# ETH.net
KiCad netlist of a schematic drawn in Altium Designer
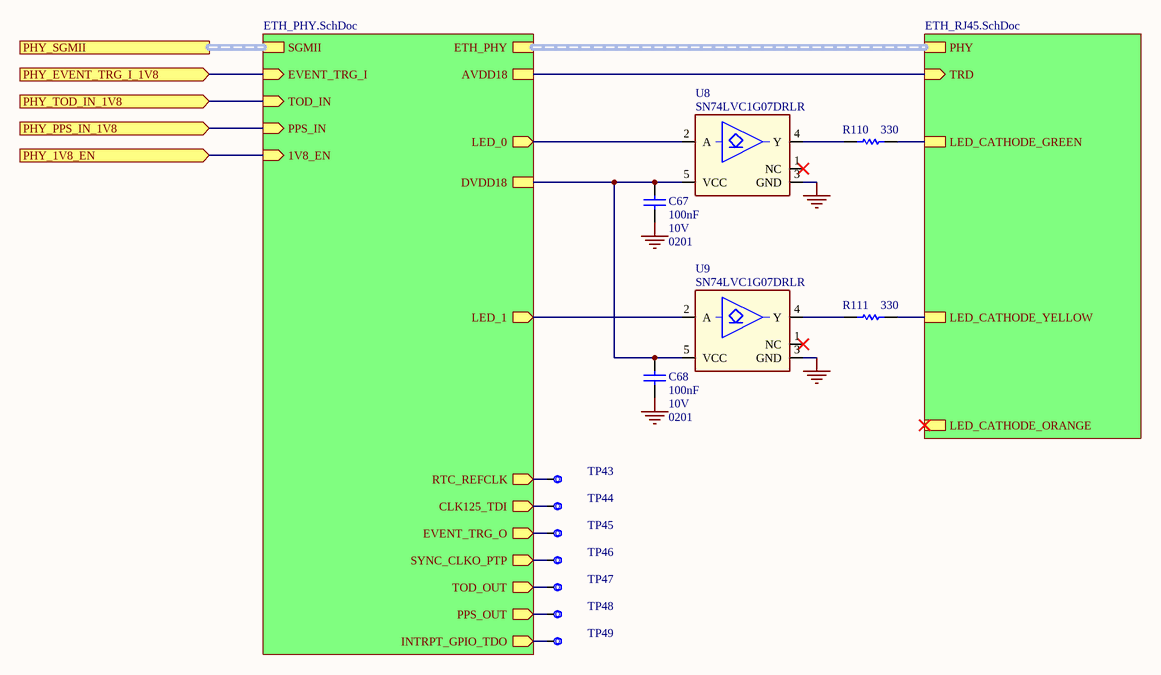
[diagram p0: ETH.SchDoc]

(export (version "E")
  (design (tool "Eeschema 10.0.6"))
  (components
    (comp (ref "C67")
      (value "100nF")
      (footprint "CAP-0201")
      (description "CAP CHIP 0201 100nF 10% 10V X5R")
      (fields
        (field (name "PART NUMBER") "CL03A104KP3NNNC")
        (field (name "MANUFACTURER") "Samsung Electro-Mechanics")
        (field (name "VOLTAGE") "10V")
        (field (name "CASE CODE (IMPERIAL)") "0201")
      )
      (libsource (lib "Clean") (part "CAP"))
    )
    (comp (ref "C68")
      (value "100nF")
      (footprint "CAP-0201")
      (description "CAP CHIP 0201 100nF 10% 10V X5R")
      (fields
        (field (name "PART NUMBER") "CL03A104KP3NNNC")
        (field (name "MANUFACTURER") "Samsung Electro-Mechanics")
        (field (name "VOLTAGE") "10V")
        (field (name "CASE CODE (IMPERIAL)") "0201")
      )
      (libsource (lib "Clean") (part "CAP"))
    )
    (comp (ref "R110")
      (value "330")
      (footprint "RES-0201")
      (description "RES CHIP 0201 330R 1% 1/20W")
      (fields (field (name "MANUFACTURER") "Yageo") (field (name "POWER") "50mW"))
      (libsource (lib "Clean") (part "RES"))
    )
    (comp (ref "R111")
      (value "330")
      (footprint "RES-0201")
      (description "RES CHIP 0201 330R 1% 1/20W")
      (fields (field (name "MANUFACTURER") "Yageo") (field (name "POWER") "50mW"))
      (libsource (lib "Clean") (part "RES"))
    )
    (comp (ref "TP43")
      (value "Test point 1.00mm")
      (footprint "TP-1.00MM")
      (fields (field (name "PART NUMBER") "This is not a component"))
      (libsource (lib "Clean") (part "TESTPOINT"))
    )
    (comp (ref "TP44")
      (value "Test point 1.00mm")
      (footprint "TP-1.00MM")
      (fields (field (name "PART NUMBER") "This is not a component"))
      (libsource (lib "Clean") (part "TESTPOINT"))
    )
    (comp (ref "TP45")
      (value "Test point 1.00mm")
      (footprint "TP-1.00MM")
      (fields (field (name "PART NUMBER") "This is not a component"))
      (libsource (lib "Clean") (part "TESTPOINT"))
    )
    (comp (ref "TP46")
      (value "Test point 1.00mm")
      (footprint "TP-1.00MM")
      (fields (field (name "PART NUMBER") "This is not a component"))
      (libsource (lib "Clean") (part "TESTPOINT"))
    )
    (comp (ref "TP47")
      (value "Test point 1.00mm")
      (footprint "TP-1.00MM")
      (fields (field (name "PART NUMBER") "This is not a component"))
      (libsource (lib "Clean") (part "TESTPOINT"))
    )
    (comp (ref "TP48")
      (value "Test point 1.00mm")
      (footprint "TP-1.00MM")
      (fields (field (name "PART NUMBER") "This is not a component"))
      (libsource (lib "Clean") (part "TESTPOINT"))
    )
    (comp (ref "TP49")
      (value "Test point 1.00mm")
      (footprint "TP-1.00MM")
      (fields (field (name "PART NUMBER") "This is not a component"))
      (libsource (lib "Clean") (part "TESTPOINT"))
    )
    (comp (ref "U8")
      (value "SN74LVC1G07DRLR")
      (footprint "TI DRL DRL0005A")
      (description "IC buffer open drain, 1.65V to 5.5V, 32mA sink current, SOT-5X3 1.6mmx1.6mm")
      (fields (field (name "MANUFACTURER") "Texas Instruments"))
      (libsource (lib "Clean") (part "SN74LVC1G07DRLR"))
    )
    (comp (ref "U9")
      (value "SN74LVC1G07DRLR")
      (footprint "TI DRL DRL0005A")
      (description "IC buffer open drain, 1.65V to 5.5V, 32mA sink current, SOT-5X3 1.6mmx1.6mm")
      (fields (field (name "MANUFACTURER") "Texas Instruments"))
      (libsource (lib "Clean") (part "SN74LVC1G07DRLR"))
    )
  )
  (nets
    (net (code "2") (name "/CLK125_TDI") (class "Default")
      (node (ref "TP44") (pin "X") (pinfunction "X_X") (pintype "passive"))
    )
    (net (code "3") (name "/DVDD18") (class "Default")
      (node (ref "C67") (pin "2") (pinfunction "2_2") (pintype "passive"))
      (node (ref "C68") (pin "2") (pinfunction "2_2") (pintype "passive"))
      (node (ref "U8") (pin "5") (pinfunction "VCC_5") (pintype "passive"))
      (node (ref "U9") (pin "5") (pinfunction "VCC_5") (pintype "passive"))
    )
    (net (code "5") (name "/EVENT_TRG_O") (class "Default")
      (node (ref "TP45") (pin "X") (pinfunction "X_X") (pintype "passive"))
    )
    (net (code "6") (name "/INTRPT_GPIO_TDO") (class "Default")
      (node (ref "TP49") (pin "X") (pinfunction "X_X") (pintype "passive"))
    )
    (net (code "7") (name "/LED_0") (class "Default")
      (node (ref "U8") (pin "2") (pinfunction "A_2") (pintype "passive"))
    )
    (net (code "8") (name "/LED_1") (class "Default")
      (node (ref "U9") (pin "2") (pinfunction "A_2") (pintype "passive"))
    )
    (net (code "9") (name "/LED_CATHODE_GREEN") (class "Default")
      (node (ref "R110") (pin "1") (pinfunction "1_1") (pintype "passive"))
    )
    (net (code "11") (name "/LED_CATHODE_YELLOW") (class "Default")
      (node (ref "R111") (pin "1") (pinfunction "1_1") (pintype "passive"))
    )
    (net (code "17") (name "/PPS_OUT") (class "Default")
      (node (ref "TP48") (pin "X") (pinfunction "X_X") (pintype "passive"))
    )
    (net (code "18") (name "/RTC_REFCLK") (class "Default")
      (node (ref "TP43") (pin "X") (pinfunction "X_X") (pintype "passive"))
    )
    (net (code "19") (name "/SYNC_CLKO_PTP") (class "Default")
      (node (ref "TP46") (pin "X") (pinfunction "X_X") (pintype "passive"))
    )
    (net (code "20") (name "/TOD_OUT") (class "Default")
      (node (ref "TP47") (pin "X") (pinfunction "X_X") (pintype "passive"))
    )
    (net (code "21") (name "GND") (class "Default")
      (node (ref "C67") (pin "1") (pinfunction "1_1") (pintype "passive"))
      (node (ref "C68") (pin "1") (pinfunction "1_1") (pintype "passive"))
      (node (ref "U8") (pin "3") (pinfunction "GND_3") (pintype "passive"))
      (node (ref "U9") (pin "3") (pinfunction "GND_3") (pintype "passive"))
    )
    (net (code "22") (name "Net-(U8-Y)") (class "Default")
      (node (ref "R110") (pin "2") (pinfunction "2_2") (pintype "passive"))
      (node (ref "U8") (pin "4") (pinfunction "Y_4") (pintype "passive"))
    )
    (net (code "23") (name "Net-(U9-Y)") (class "Default")
      (node (ref "R111") (pin "2") (pinfunction "2_2") (pintype "passive"))
      (node (ref "U9") (pin "4") (pinfunction "Y_4") (pintype "passive"))
    )
    (net (code "24") (name "unconnected-(U8-NC-Pad1)") (class "Default")
      (node (ref "U8") (pin "1") (pinfunction "NC_1") (pintype "passive+no_connect"))
    )
    (net (code "25") (name "unconnected-(U9-NC-Pad1)") (class "Default")
      (node (ref "U9") (pin "1") (pinfunction "NC_1") (pintype "passive+no_connect"))
    )
  )
)
